# PAGE2.net
KiCad netlist of a schematic drawn in Altium Designer
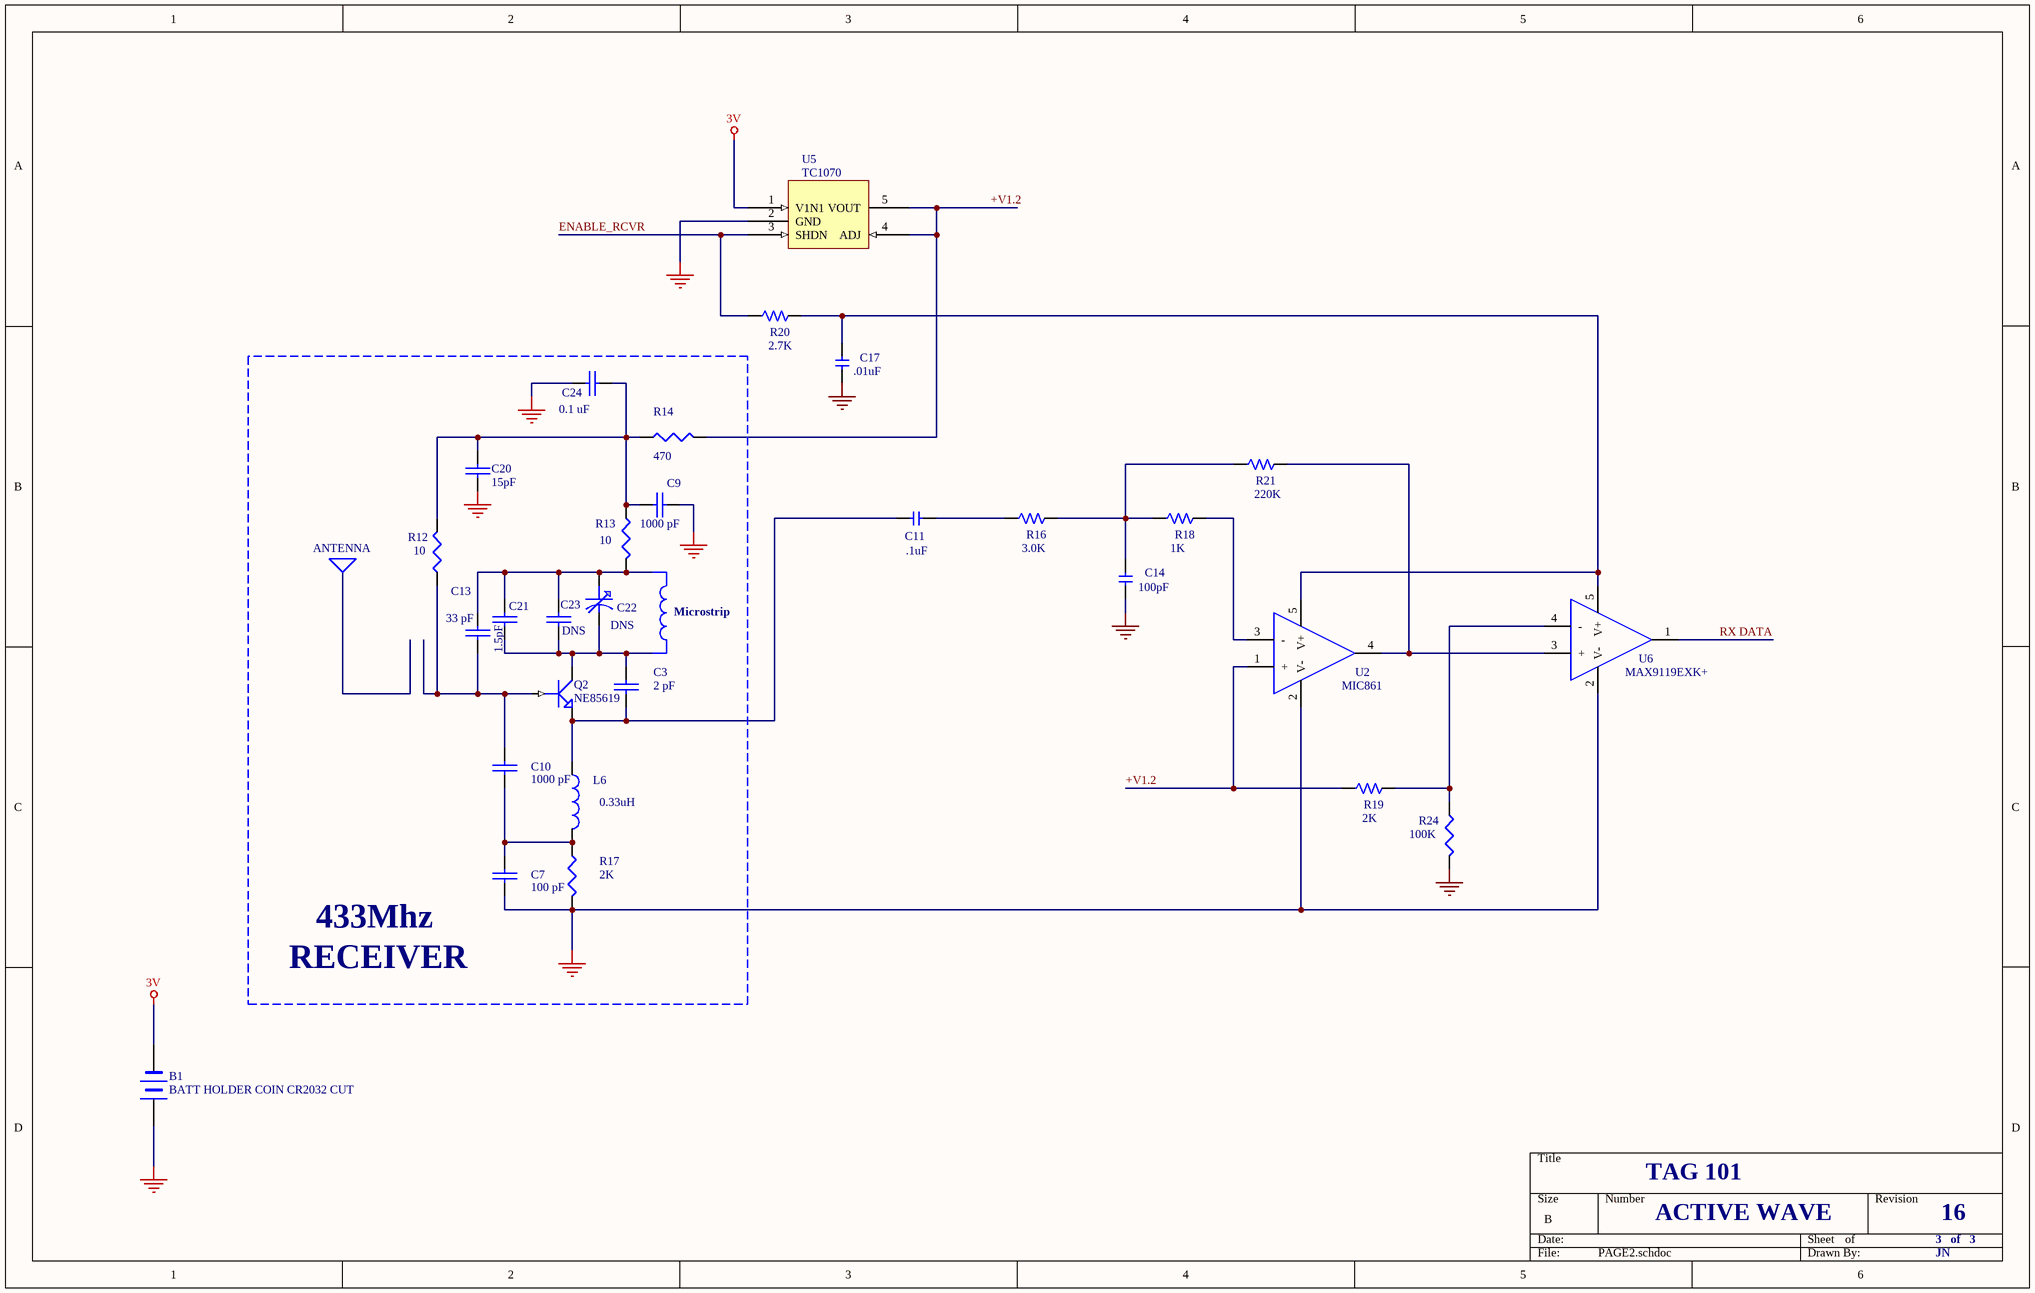
[diagram p0: PAGE2.schdoc]

(export (version "E")
  (design (tool "Eeschema 10.0.6"))
  (components
    (comp (ref "B1")
      (value "BATT HOLDER COIN CR2032 CUT")
      (footprint "BATTERY COIN CR2032")
      (description "Battery")
      (libsource (lib "*") (part "BATTERY"))
    )
    (comp (ref "C3")
      (value "2 pF")
      (footprint "0603")
      (description "Capacitor")
      (libsource (lib "*") (part "CAP"))
    )
    (comp (ref "C7")
      (value "100 pF")
      (footprint "0603")
      (description "Capacitor")
      (libsource (lib "*") (part "CAP"))
    )
    (comp (ref "C9")
      (value "1000 pF")
      (footprint "0603")
      (description "Capacitor")
      (libsource (lib "*") (part "CAP"))
    )
    (comp (ref "C10")
      (value "1000 pF")
      (footprint "0603")
      (description "Capacitor")
      (libsource (lib "*") (part "CAP"))
    )
    (comp (ref "C11") (value ".1uF") (footprint "0603") (libsource (lib "*") (part "C")))
    (comp (ref "C13")
      (value "33 pF")
      (footprint "0603")
      (description "Capacitor")
      (libsource (lib "*") (part "CAP"))
    )
    (comp (ref "C14") (value "100pF") (footprint "0603") (libsource (lib "*") (part "C")))
    (comp (ref "C17") (value ".01uF") (footprint "0603") (libsource (lib "*") (part "C")))
    (comp (ref "C20")
      (value "15pF")
      (footprint "0603")
      (description "Capacitor")
      (libsource (lib "*") (part "CAP"))
    )
    (comp (ref "C21")
      (value "1.5pF")
      (footprint "0603")
      (description "Capacitor")
      (libsource (lib "*") (part "CAP"))
    )
    (comp (ref "C22") (value "DNS") (footprint "0603") (libsource (lib "*") (part "CAPACITOR VAR")))
    (comp (ref "C23")
      (value "DNS")
      (footprint "0603")
      (description "Capacitor")
      (libsource (lib "*") (part "CAP"))
    )
    (comp (ref "C24")
      (value "0.1 uF")
      (footprint "0603")
      (description "Capacitor")
      (libsource (lib "*") (part "CAP"))
    )
    (comp (ref "L6") (value "0.33uH") (footprint "0603") (libsource (lib "*") (part "INDUCTOR")))
    (comp (ref "Q2")
      (value "NE85619")
      (footprint "3 PIN ULTRA SUPER MINI MOLD")
      (description "NPN Transistor")
      (libsource (lib "*") (part "NPN1"))
    )
    (comp (ref "R12") (value "10") (footprint "0603") (libsource (lib "*") (part "R")))
    (comp (ref "R13") (value "10") (footprint "0603") (libsource (lib "*") (part "R")))
    (comp (ref "R14") (value "470") (footprint "0603") (libsource (lib "*") (part "R")))
    (comp (ref "R16") (value "3.0K") (footprint "0603") (libsource (lib "") (part "R_1")))
    (comp (ref "R17") (value "2K") (footprint "0603") (libsource (lib "*") (part "RESISTOR")))
    (comp (ref "R18") (value "1K") (footprint "0603") (libsource (lib "") (part "R_1")))
    (comp (ref "R19") (value "2K") (footprint "0603") (libsource (lib "") (part "R_1")))
    (comp (ref "R20") (value "2.7K") (footprint "0603") (libsource (lib "") (part "R_1")))
    (comp (ref "R21") (value "220K") (footprint "0603") (libsource (lib "") (part "R_1")))
    (comp (ref "R24") (value "100K") (footprint "0603") (libsource (lib "*") (part "R")))
    (comp (ref "U2") (value "MIC861") (libsource (lib "*") (part "OPAMP MIC861")))
    (comp (ref "U5") (value "TC1070") (footprint "SOT23-5A") (libsource (lib "*") (part "TC1070-2")))
    (comp (ref "U6")
      (value "MAX9119EXK+")
      (footprint "SC70")
      (libsource (lib "*") (part "COMPARATOR MAX9117"))
    )
  )
  (nets
    (net (code "1") (name "/+V1.2") (class "Default")
      (node (ref "R14") (pin "2") (pinfunction "2_2") (pintype "passive"))
      (node (ref "R19") (pin "1") (pinfunction "1_1") (pintype "passive"))
      (node (ref "U2") (pin "1") (pinfunction "+_1") (pintype "passive"))
      (node (ref "U5") (pin "4") (pinfunction "ADJ_4") (pintype "input"))
      (node (ref "U5") (pin "5") (pinfunction "VOUT_5") (pintype "power_in"))
    )
    (net (code "2") (name "/ENABLE_RCVR") (class "Default")
      (node (ref "R20") (pin "1") (pinfunction "1_1") (pintype "passive"))
      (node (ref "U5") (pin "3") (pinfunction "SHDN_3") (pintype "input"))
    )
    (net (code "3") (name "/RX DATA") (class "Default")
      (node (ref "U6") (pin "1") (pinfunction "OUT_1") (pintype "passive"))
    )
    (net (code "4") (name "3V") (class "Default")
      (node (ref "B1") (pin "1") (pinfunction "-_1") (pintype "passive"))
      (node (ref "U5") (pin "1") (pinfunction "V1N1_1") (pintype "input"))
    )
    (net (code "5") (name "GND") (class "Default")
      (node (ref "B1") (pin "2") (pinfunction "+_2") (pintype "passive"))
      (node (ref "C14") (pin "1") (pinfunction "1_1") (pintype "passive"))
      (node (ref "C17") (pin "1") (pinfunction "1_1") (pintype "passive"))
      (node (ref "C20") (pin "1") (pinfunction "1_1") (pintype "passive"))
      (node (ref "C24") (pin "1") (pinfunction "1_1") (pintype "passive"))
      (node (ref "C7") (pin "2") (pinfunction "2_2") (pintype "passive"))
      (node (ref "C9") (pin "2") (pinfunction "2_2") (pintype "passive"))
      (node (ref "R17") (pin "2") (pinfunction "2_2") (pintype "passive"))
      (node (ref "R24") (pin "2") (pinfunction "2_2") (pintype "passive"))
      (node (ref "U2") (pin "2") (pinfunction "V-_2") (pintype "passive"))
      (node (ref "U5") (pin "2") (pinfunction "GND_2") (pintype "power_in"))
      (node (ref "U6") (pin "2") (pinfunction "V-_2") (pintype "passive"))
    )
    (net (code "6") (name "Net-(C10-Pad1)") (class "Default")
      (node (ref "C10") (pin "1") (pinfunction "1_1") (pintype "passive"))
      (node (ref "C13") (pin "1") (pinfunction "1_1") (pintype "passive"))
      (node (ref "Q2") (pin "B") (pinfunction "B_B") (pintype "input"))
      (node (ref "R12") (pin "1") (pinfunction "1_1") (pintype "passive"))
    )
    (net (code "7") (name "Net-(C10-Pad2)") (class "Default")
      (node (ref "C10") (pin "2") (pinfunction "2_2") (pintype "passive"))
      (node (ref "C7") (pin "1") (pinfunction "1_1") (pintype "passive"))
      (node (ref "L6") (pin "2") (pinfunction "2_2") (pintype "passive"))
      (node (ref "R17") (pin "1") (pinfunction "1_1") (pintype "passive"))
    )
    (net (code "8") (name "Net-(C11-Pad1)") (class "Default")
      (node (ref "C11") (pin "1") (pinfunction "1_1") (pintype "passive"))
      (node (ref "C3") (pin "2") (pinfunction "2_2") (pintype "passive"))
      (node (ref "L6") (pin "1") (pinfunction "1_1") (pintype "passive"))
      (node (ref "Q2") (pin "E") (pinfunction "E_E") (pintype "passive"))
    )
    (net (code "9") (name "Net-(C11-Pad2)") (class "Default")
      (node (ref "C11") (pin "2") (pinfunction "2_2") (pintype "passive"))
      (node (ref "R16") (pin "1") (pinfunction "1_1") (pintype "passive"))
    )
    (net (code "10") (name "Net-(C13-Pad2)") (class "Default")
      (node (ref "C13") (pin "2") (pinfunction "2_2") (pintype "passive"))
      (node (ref "C21") (pin "1") (pinfunction "1_1") (pintype "passive"))
      (node (ref "C22") (pin "1") (pinfunction "1_1") (pintype "passive"))
      (node (ref "C23") (pin "1") (pinfunction "1_1") (pintype "passive"))
      (node (ref "R13") (pin "2") (pinfunction "2_2") (pintype "passive"))
    )
    (net (code "11") (name "Net-(C14-Pad2)") (class "Default")
      (node (ref "C14") (pin "2") (pinfunction "2_2") (pintype "passive"))
      (node (ref "R16") (pin "2") (pinfunction "2_2") (pintype "passive"))
      (node (ref "R18") (pin "1") (pinfunction "1_1") (pintype "passive"))
      (node (ref "R21") (pin "1") (pinfunction "1_1") (pintype "passive"))
    )
    (net (code "12") (name "Net-(C20-Pad2)") (class "Default")
      (node (ref "C20") (pin "2") (pinfunction "2_2") (pintype "passive"))
      (node (ref "C24") (pin "2") (pinfunction "2_2") (pintype "passive"))
      (node (ref "C9") (pin "1") (pinfunction "1_1") (pintype "passive"))
      (node (ref "R12") (pin "2") (pinfunction "2_2") (pintype "passive"))
      (node (ref "R13") (pin "1") (pinfunction "1_1") (pintype "passive"))
      (node (ref "R14") (pin "1") (pinfunction "1_1") (pintype "passive"))
    )
    (net (code "13") (name "Net-(C21-Pad2)") (class "Default")
      (node (ref "C21") (pin "2") (pinfunction "2_2") (pintype "passive"))
      (node (ref "C22") (pin "2") (pinfunction "2_2") (pintype "passive"))
      (node (ref "C23") (pin "2") (pinfunction "2_2") (pintype "passive"))
      (node (ref "C3") (pin "1") (pinfunction "1_1") (pintype "passive"))
      (node (ref "Q2") (pin "C") (pinfunction "C_C") (pintype "passive"))
    )
    (net (code "14") (name "Net-(U2--)") (class "Default")
      (node (ref "R18") (pin "2") (pinfunction "2_2") (pintype "passive"))
      (node (ref "U2") (pin "3") (pinfunction "-_3") (pintype "passive"))
    )
    (net (code "15") (name "Net-(U2-OUT)") (class "Default")
      (node (ref "R21") (pin "2") (pinfunction "2_2") (pintype "passive"))
      (node (ref "U2") (pin "4") (pinfunction "OUT_4") (pintype "passive"))
      (node (ref "U6") (pin "3") (pinfunction "+_3") (pintype "passive"))
    )
    (net (code "16") (name "Net-(U2-V+)") (class "Default")
      (node (ref "C17") (pin "2") (pinfunction "2_2") (pintype "passive"))
      (node (ref "R20") (pin "2") (pinfunction "2_2") (pintype "passive"))
      (node (ref "U2") (pin "5") (pinfunction "V+_5") (pintype "passive"))
      (node (ref "U6") (pin "5") (pinfunction "V+_5") (pintype "passive"))
    )
    (net (code "17") (name "Net-(U6--)") (class "Default")
      (node (ref "R19") (pin "2") (pinfunction "2_2") (pintype "passive"))
      (node (ref "R24") (pin "1") (pinfunction "1_1") (pintype "passive"))
      (node (ref "U6") (pin "4") (pinfunction "-_4") (pintype "passive"))
    )
  )
)
